# uven2-mk3-lid-switch.net
KiCad netlist of a schematic drawn in EasyEDA Pro
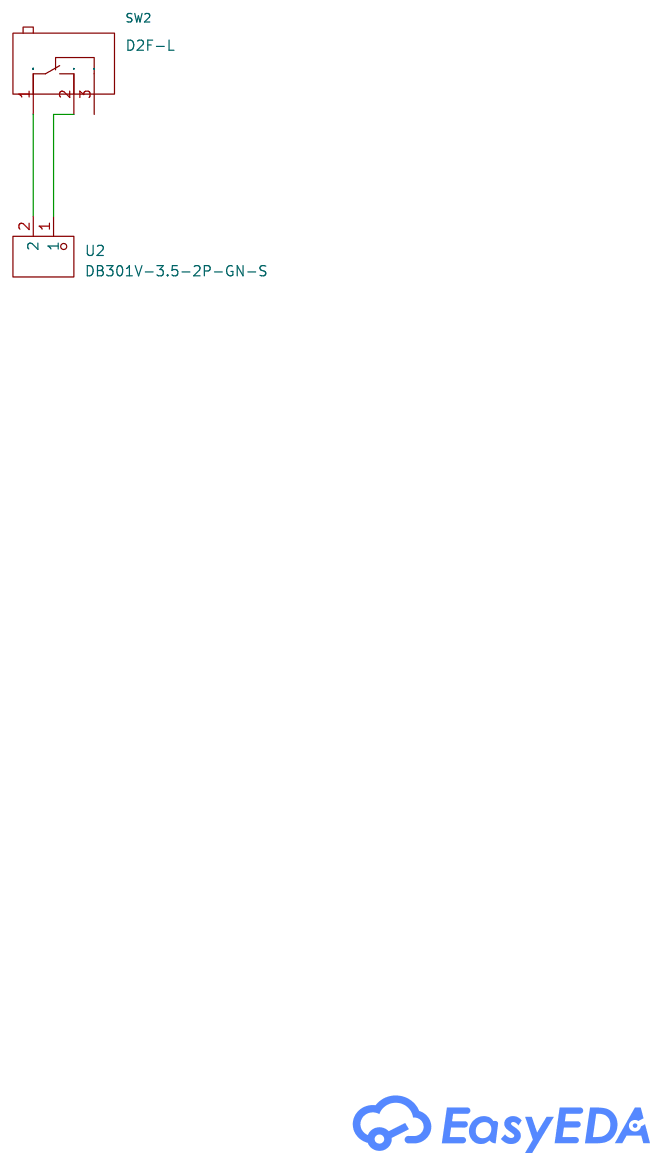
[diagram p0: schematic sheet]

(export (version "E")
  (design (tool "Eeschema 10.0.6"))
  (components
    (comp (ref "SW2")
      (value "D2F-L")
      (footprint "easyedapro:SW-TH_D2F-L")
      (fields (field (name "Manufacturer") "OMRON(欧姆龙)"))
      (libsource (lib "easyedapro") (part "D2F-L"))
    )
    (comp (ref "U2")
      (value "DB301V-3.5-2P-GN-S")
      (footprint "easyedapro:CONN-TH_DB301V-3.5-2P-GN")
      (fields (field (name "Manufacturer") "DORABO(地博电气)"))
      (libsource (lib "easyedapro") (part "DB301V-3.5-2P-GN"))
    )
  )
  (nets
    (net (code "1") (name "Net-(SW2-COM)") (class "Default")
      (node (ref "SW2") (pin "1") (pinfunction "COM_1") (pintype "input"))
      (node (ref "U2") (pin "2") (pinfunction "2_2") (pintype "unspecified"))
    )
    (net (code "2") (name "Net-(SW2-NO)") (class "Default")
      (node (ref "SW2") (pin "2") (pinfunction "NO_2") (pintype "input"))
      (node (ref "U2") (pin "1") (pinfunction "1_1") (pintype "unspecified"))
    )
    (net (code "3") (name "unconnected-(SW2-NC-Pad3)") (class "Default")
      (node (ref "SW2") (pin "3") (pinfunction "NC_3") (pintype "input"))
    )
  )
)
